# E_LELE.net
KiCad netlist of a schematic drawn in EAGLE
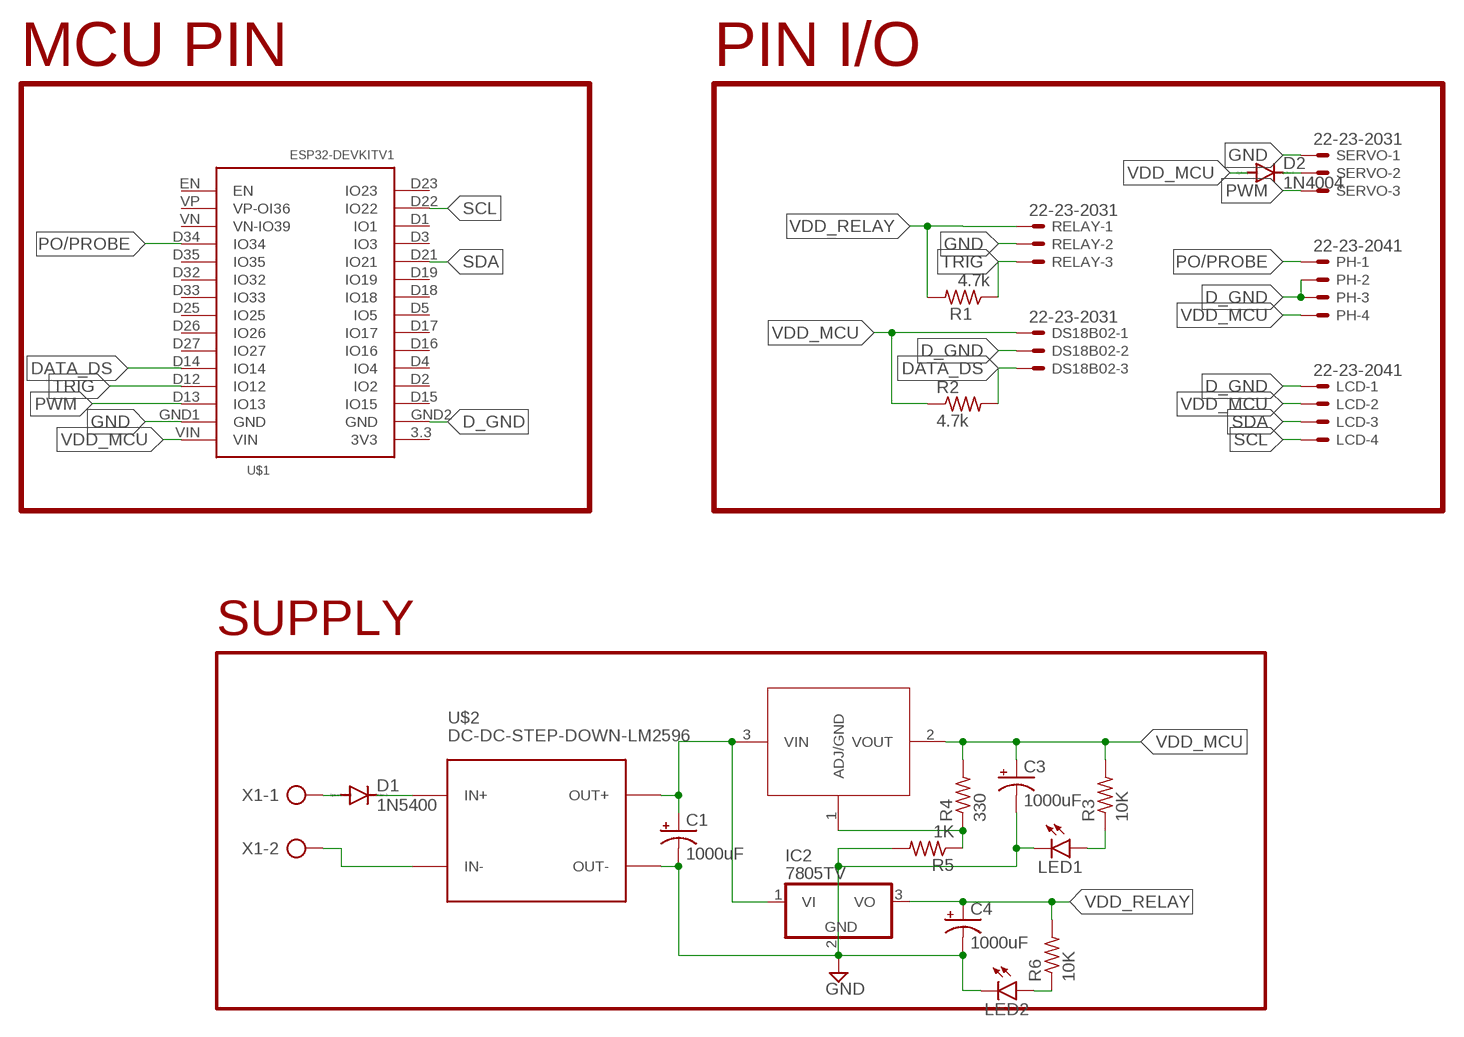
[diagram p0: schematic, sheet 1]

(export (version "E")
  (design (tool "Eeschema 10.0.6"))
  (components
    (comp (ref "C1")
      (value "1000uF")
      (footprint "eagle-import:E5-10,5")
      (libsource (lib "eagle-import") (part "CPOL-USE5-10.5"))
    )
    (comp (ref "C3")
      (value "1000uF")
      (footprint "eagle-import:E5-10,5")
      (libsource (lib "eagle-import") (part "CPOL-USE5-10.5"))
    )
    (comp (ref "C4")
      (value "1000uF")
      (footprint "eagle-import:E5-10,5")
      (libsource (lib "eagle-import") (part "CPOL-USE5-10.5"))
    )
    (comp (ref "D1")
      (value "1N5400")
      (footprint "eagle-import:DO201-15")
      (libsource (lib "eagle-import") (part "1N5400"))
    )
    (comp (ref "D2")
      (value "1N4004")
      (footprint "eagle-import:DO41-10")
      (libsource (lib "eagle-import") (part "1N4004"))
    )
    (comp (ref "DS18B02")
      (value "22-23-2031")
      (footprint "eagle-import:22-23-2031")
      (fields (field (name "MF") "MOLEX"))
      (libsource (lib "eagle-import") (part "22-23-2031"))
    )
    (comp (ref "IC2")
      (value "7805TV")
      (footprint "eagle-import:TO220V")
      (libsource (lib "eagle-import") (part "78TV05"))
    )
    (comp (ref "LCD")
      (value "22-23-2041")
      (footprint "eagle-import:22-23-2041")
      (fields (field (name "MF") "MOLEX"))
      (libsource (lib "eagle-import") (part "22-23-2041"))
    )
    (comp (ref "LED1")
      (value "LED3MM")
      (footprint "eagle-import:LED3MM")
      (libsource (lib "eagle-import") (part "LED3MM"))
    )
    (comp (ref "LED2")
      (value "LED3MM")
      (footprint "eagle-import:LED3MM")
      (libsource (lib "eagle-import") (part "LED3MM"))
    )
    (comp (ref "LM338T")
      (value "LM1084IT-5.0")
      (footprint "eagle-import:T03B_TEX")
      (fields (field (name "COPYRIGHT") "Copyright (C) 2018 Accelerated Designs. All rights reserved"))
      (libsource (lib "eagle-import") (part "LM1084IT-5.0"))
    )
    (comp (ref "PH")
      (value "22-23-2041")
      (footprint "eagle-import:22-23-2041")
      (fields (field (name "MF") "MOLEX"))
      (libsource (lib "eagle-import") (part "22-23-2041"))
    )
    (comp (ref "R1")
      (value "4.7k")
      (footprint "eagle-import:0204_7")
      (libsource (lib "eagle-import") (part "R-US_0204/7"))
    )
    (comp (ref "R2")
      (value "4.7k")
      (footprint "eagle-import:0204_7")
      (libsource (lib "eagle-import") (part "R-US_0204/7"))
    )
    (comp (ref "R3")
      (value "10K")
      (footprint "eagle-import:0204_7")
      (libsource (lib "eagle-import") (part "R-US_0204/7"))
    )
    (comp (ref "R4")
      (value "330")
      (footprint "eagle-import:0204_7")
      (libsource (lib "eagle-import") (part "R-US_0204/7"))
    )
    (comp (ref "R5")
      (value "1K")
      (footprint "eagle-import:0204_7")
      (libsource (lib "eagle-import") (part "R-US_0204/7"))
    )
    (comp (ref "R6")
      (value "10K")
      (footprint "eagle-import:0204_7")
      (libsource (lib "eagle-import") (part "R-US_0204/7"))
    )
    (comp (ref "RELAY")
      (value "22-23-2031")
      (footprint "eagle-import:22-23-2031")
      (fields (field (name "MF") "MOLEX"))
      (libsource (lib "eagle-import") (part "22-23-2031"))
    )
    (comp (ref "SERVO")
      (value "22-23-2031")
      (footprint "eagle-import:22-23-2031")
      (fields (field (name "MF") "MOLEX"))
      (libsource (lib "eagle-import") (part "22-23-2031"))
    )
    (comp (ref "U$1")
      (value "ESP32DEVKITV1")
      (footprint "eagle-import:ESP32-DEVKITV1")
      (libsource (lib "eagle-import") (part "ESP32DEVKITV1"))
    )
    (comp (ref "U$2")
      (value "DC-DC-STEP-DOWN-LM2596")
      (footprint "eagle-import:DC-DC-STEP-DOWN-LM2596")
      (libsource (lib "eagle-import") (part "DC-DC-STEP-DOWN-LM2596"))
    )
    (comp (ref "X1")
      (value "AK500/2")
      (footprint "eagle-import:AK500_2")
      (libsource (lib "eagle-import") (part "AK500/2"))
    )
  )
  (nets
    (net (code "1") (name "DATA_DS") (class "Default")
      (node (ref "DS18B02") (pin "3") (pinfunction "S_3") (pintype "passive"))
      (node (ref "R2") (pin "2") (pinfunction "2_2") (pintype "passive"))
      (node (ref "U$1") (pin "D14") (pinfunction "IO14_D14") (pintype "bidirectional"))
    )
    (net (code "2") (name "D_GND") (class "Default")
      (node (ref "DS18B02") (pin "2") (pinfunction "S_2") (pintype "passive"))
      (node (ref "LCD") (pin "1") (pinfunction "S_1") (pintype "passive"))
      (node (ref "PH") (pin "2") (pinfunction "S_2") (pintype "passive"))
      (node (ref "PH") (pin "3") (pinfunction "S_3") (pintype "passive"))
      (node (ref "U$1") (pin "GND2") (pinfunction "GND_GND2") (pintype "bidirectional"))
    )
    (net (code "3") (name "GND") (class "Default")
      (node (ref "C1") (pin "-") (pinfunction "-_-") (pintype "passive"))
      (node (ref "C3") (pin "-") (pinfunction "-_-") (pintype "passive"))
      (node (ref "C4") (pin "-") (pinfunction "-_-") (pintype "passive"))
      (node (ref "IC2") (pin "2") (pinfunction "GND_2") (pintype "passive"))
      (node (ref "LED1") (pin "K") (pinfunction "C_K") (pintype "passive"))
      (node (ref "LED2") (pin "K") (pinfunction "C_K") (pintype "passive"))
      (node (ref "R5") (pin "2") (pinfunction "2_2") (pintype "passive"))
      (node (ref "RELAY") (pin "2") (pinfunction "S_2") (pintype "passive"))
      (node (ref "SERVO") (pin "1") (pinfunction "S_1") (pintype "passive"))
      (node (ref "U$1") (pin "GND1") (pinfunction "GND_GND1") (pintype "bidirectional"))
      (node (ref "U$2") (pin "OUT-") (pinfunction "OUT-_OUT-") (pintype "bidirectional"))
    )
    (net (code "4") (name "Net-(D1-PadC)") (class "Default")
      (node (ref "D1") (pin "C") (pinfunction "C_C") (pintype "passive"))
      (node (ref "U$2") (pin "IN+") (pinfunction "IN+_IN+") (pintype "bidirectional"))
    )
    (net (code "5") (name "Net-(IC2-VI)") (class "Default")
      (node (ref "C1") (pin "+") (pinfunction "+_+") (pintype "passive"))
      (node (ref "IC2") (pin "1") (pinfunction "VI_1") (pintype "input"))
      (node (ref "LM338T") (pin "3") (pinfunction "VIN_3") (pintype "input"))
      (node (ref "U$2") (pin "OUT+") (pinfunction "OUT+_OUT+") (pintype "bidirectional"))
    )
    (net (code "6") (name "Net-(LED1-PadA)") (class "Default")
      (node (ref "LED1") (pin "A") (pinfunction "A_A") (pintype "passive"))
      (node (ref "R3") (pin "1") (pinfunction "1_1") (pintype "passive"))
    )
    (net (code "7") (name "Net-(LED2-PadA)") (class "Default")
      (node (ref "LED2") (pin "A") (pinfunction "A_A") (pintype "passive"))
      (node (ref "R6") (pin "1") (pinfunction "1_1") (pintype "passive"))
    )
    (net (code "8") (name "Net-(LM338T-ADJ{slash}GND)") (class "Default")
      (node (ref "LM338T") (pin "1") (pinfunction "ADJ/GND_1") (pintype "passive"))
      (node (ref "R4") (pin "1") (pinfunction "1_1") (pintype "passive"))
      (node (ref "R5") (pin "1") (pinfunction "1_1") (pintype "passive"))
    )
    (net (code "9") (name "Net-(SERVOB-S)") (class "Default")
      (node (ref "D2") (pin "C") (pinfunction "C_C") (pintype "passive"))
      (node (ref "SERVO") (pin "2") (pinfunction "S_2") (pintype "passive"))
    )
    (net (code "10") (name "Net-(X1A-KL)") (class "Default")
      (node (ref "D1") (pin "A") (pinfunction "A_A") (pintype "passive"))
      (node (ref "X1") (pin "1") (pinfunction "KL_1") (pintype "passive"))
    )
    (net (code "11") (name "Net-(X1B-KL)") (class "Default")
      (node (ref "U$2") (pin "IN-") (pinfunction "IN-_IN-") (pintype "bidirectional"))
      (node (ref "X1") (pin "2") (pinfunction "KL_2") (pintype "passive"))
    )
    (net (code "12") (name "PO{slash}PROBE") (class "Default")
      (node (ref "PH") (pin "1") (pinfunction "S_1") (pintype "passive"))
      (node (ref "U$1") (pin "D34") (pinfunction "IO34_D34") (pintype "bidirectional"))
    )
    (net (code "13") (name "PWM") (class "Default")
      (node (ref "SERVO") (pin "3") (pinfunction "S_3") (pintype "passive"))
      (node (ref "U$1") (pin "D13") (pinfunction "IO13_D13") (pintype "bidirectional"))
    )
    (net (code "14") (name "SCL") (class "Default")
      (node (ref "LCD") (pin "4") (pinfunction "S_4") (pintype "passive"))
      (node (ref "U$1") (pin "D22") (pinfunction "IO22_D22") (pintype "bidirectional"))
    )
    (net (code "15") (name "SDA") (class "Default")
      (node (ref "LCD") (pin "3") (pinfunction "S_3") (pintype "passive"))
      (node (ref "U$1") (pin "D21") (pinfunction "IO21_D21") (pintype "bidirectional"))
    )
    (net (code "16") (name "TRIG") (class "Default")
      (node (ref "R1") (pin "1") (pinfunction "1_1") (pintype "passive"))
      (node (ref "RELAY") (pin "3") (pinfunction "S_3") (pintype "passive"))
      (node (ref "U$1") (pin "D12") (pinfunction "IO12_D12") (pintype "bidirectional"))
    )
    (net (code "17") (name "VDD_MCU") (class "Default")
      (node (ref "C3") (pin "+") (pinfunction "+_+") (pintype "passive"))
      (node (ref "D2") (pin "A") (pinfunction "A_A") (pintype "passive"))
      (node (ref "DS18B02") (pin "1") (pinfunction "S_1") (pintype "passive"))
      (node (ref "LCD") (pin "2") (pinfunction "S_2") (pintype "passive"))
      (node (ref "LM338T") (pin "2") (pinfunction "VOUT_2") (pintype "output"))
      (node (ref "PH") (pin "4") (pinfunction "S_4") (pintype "passive"))
      (node (ref "R2") (pin "1") (pinfunction "1_1") (pintype "passive"))
      (node (ref "R3") (pin "2") (pinfunction "2_2") (pintype "passive"))
      (node (ref "R4") (pin "2") (pinfunction "2_2") (pintype "passive"))
      (node (ref "U$1") (pin "VIN") (pinfunction "VIN_VIN") (pintype "bidirectional"))
    )
    (net (code "18") (name "VDD_RELAY") (class "Default")
      (node (ref "C4") (pin "+") (pinfunction "+_+") (pintype "passive"))
      (node (ref "IC2") (pin "3") (pinfunction "VO_3") (pintype "passive"))
      (node (ref "R1") (pin "2") (pinfunction "2_2") (pintype "passive"))
      (node (ref "R6") (pin "2") (pinfunction "2_2") (pintype "passive"))
      (node (ref "RELAY") (pin "1") (pinfunction "S_1") (pintype "passive"))
    )
    (net (code "19") (name "unconnected-(U$1-3V3-Pad3.3)") (class "Default")
      (node (ref "U$1") (pin "3.3") (pinfunction "3V3_3.3") (pintype "bidirectional"))
    )
    (net (code "20") (name "unconnected-(U$1-IO1-PadD1)") (class "Default")
      (node (ref "U$1") (pin "D1") (pinfunction "IO1_D1") (pintype "bidirectional"))
    )
    (net (code "21") (name "unconnected-(U$1-IO2-PadD2)") (class "Default")
      (node (ref "U$1") (pin "D2") (pinfunction "IO2_D2") (pintype "bidirectional"))
    )
    (net (code "22") (name "unconnected-(U$1-IO3-PadD3)") (class "Default")
      (node (ref "U$1") (pin "D3") (pinfunction "IO3_D3") (pintype "bidirectional"))
    )
    (net (code "23") (name "unconnected-(U$1-IO4-PadD4)") (class "Default")
      (node (ref "U$1") (pin "D4") (pinfunction "IO4_D4") (pintype "bidirectional"))
    )
    (net (code "24") (name "unconnected-(U$1-IO5-PadD5)") (class "Default")
      (node (ref "U$1") (pin "D5") (pinfunction "IO5_D5") (pintype "bidirectional"))
    )
    (net (code "25") (name "unconnected-(U$1-IO15-PadD15)") (class "Default")
      (node (ref "U$1") (pin "D15") (pinfunction "IO15_D15") (pintype "bidirectional"))
    )
    (net (code "26") (name "unconnected-(U$1-IO16-PadD16)") (class "Default")
      (node (ref "U$1") (pin "D16") (pinfunction "IO16_D16") (pintype "bidirectional"))
    )
    (net (code "27") (name "unconnected-(U$1-IO17-PadD17)") (class "Default")
      (node (ref "U$1") (pin "D17") (pinfunction "IO17_D17") (pintype "bidirectional"))
    )
    (net (code "28") (name "unconnected-(U$1-IO18-PadD18)") (class "Default")
      (node (ref "U$1") (pin "D18") (pinfunction "IO18_D18") (pintype "bidirectional"))
    )
    (net (code "29") (name "unconnected-(U$1-IO19-PadD19)") (class "Default")
      (node (ref "U$1") (pin "D19") (pinfunction "IO19_D19") (pintype "bidirectional"))
    )
    (net (code "30") (name "unconnected-(U$1-IO23-PadD23)") (class "Default")
      (node (ref "U$1") (pin "D23") (pinfunction "IO23_D23") (pintype "bidirectional"))
    )
    (net (code "31") (name "unconnected-(U$1-IO25-PadD25)") (class "Default")
      (node (ref "U$1") (pin "D25") (pinfunction "IO25_D25") (pintype "bidirectional"))
    )
    (net (code "32") (name "unconnected-(U$1-IO26-PadD26)") (class "Default")
      (node (ref "U$1") (pin "D26") (pinfunction "IO26_D26") (pintype "bidirectional"))
    )
    (net (code "33") (name "unconnected-(U$1-IO27-PadD27)") (class "Default")
      (node (ref "U$1") (pin "D27") (pinfunction "IO27_D27") (pintype "bidirectional"))
    )
    (net (code "34") (name "unconnected-(U$1-IO32-PadD32)") (class "Default")
      (node (ref "U$1") (pin "D32") (pinfunction "IO32_D32") (pintype "bidirectional"))
    )
    (net (code "35") (name "unconnected-(U$1-IO33-PadD33)") (class "Default")
      (node (ref "U$1") (pin "D33") (pinfunction "IO33_D33") (pintype "bidirectional"))
    )
    (net (code "36") (name "unconnected-(U$1-IO35-PadD35)") (class "Default")
      (node (ref "U$1") (pin "D35") (pinfunction "IO35_D35") (pintype "bidirectional"))
    )
    (net (code "37") (name "unconnected-(U$1-PadEN)") (class "Default")
      (node (ref "U$1") (pin "EN") (pinfunction "EN_EN") (pintype "bidirectional"))
    )
    (net (code "38") (name "unconnected-(U$1-VN-IO39-PadVN)") (class "Default")
      (node (ref "U$1") (pin "VN") (pinfunction "VN-IO39_VN") (pintype "bidirectional"))
    )
    (net (code "39") (name "unconnected-(U$1-VP-OI36-PadVP)") (class "Default")
      (node (ref "U$1") (pin "VP") (pinfunction "VP-OI36_VP") (pintype "bidirectional"))
    )
  )
)
